# XL_N76E003K2__POWER_V17.net
KiCad netlist of a schematic drawn in Altium Designer
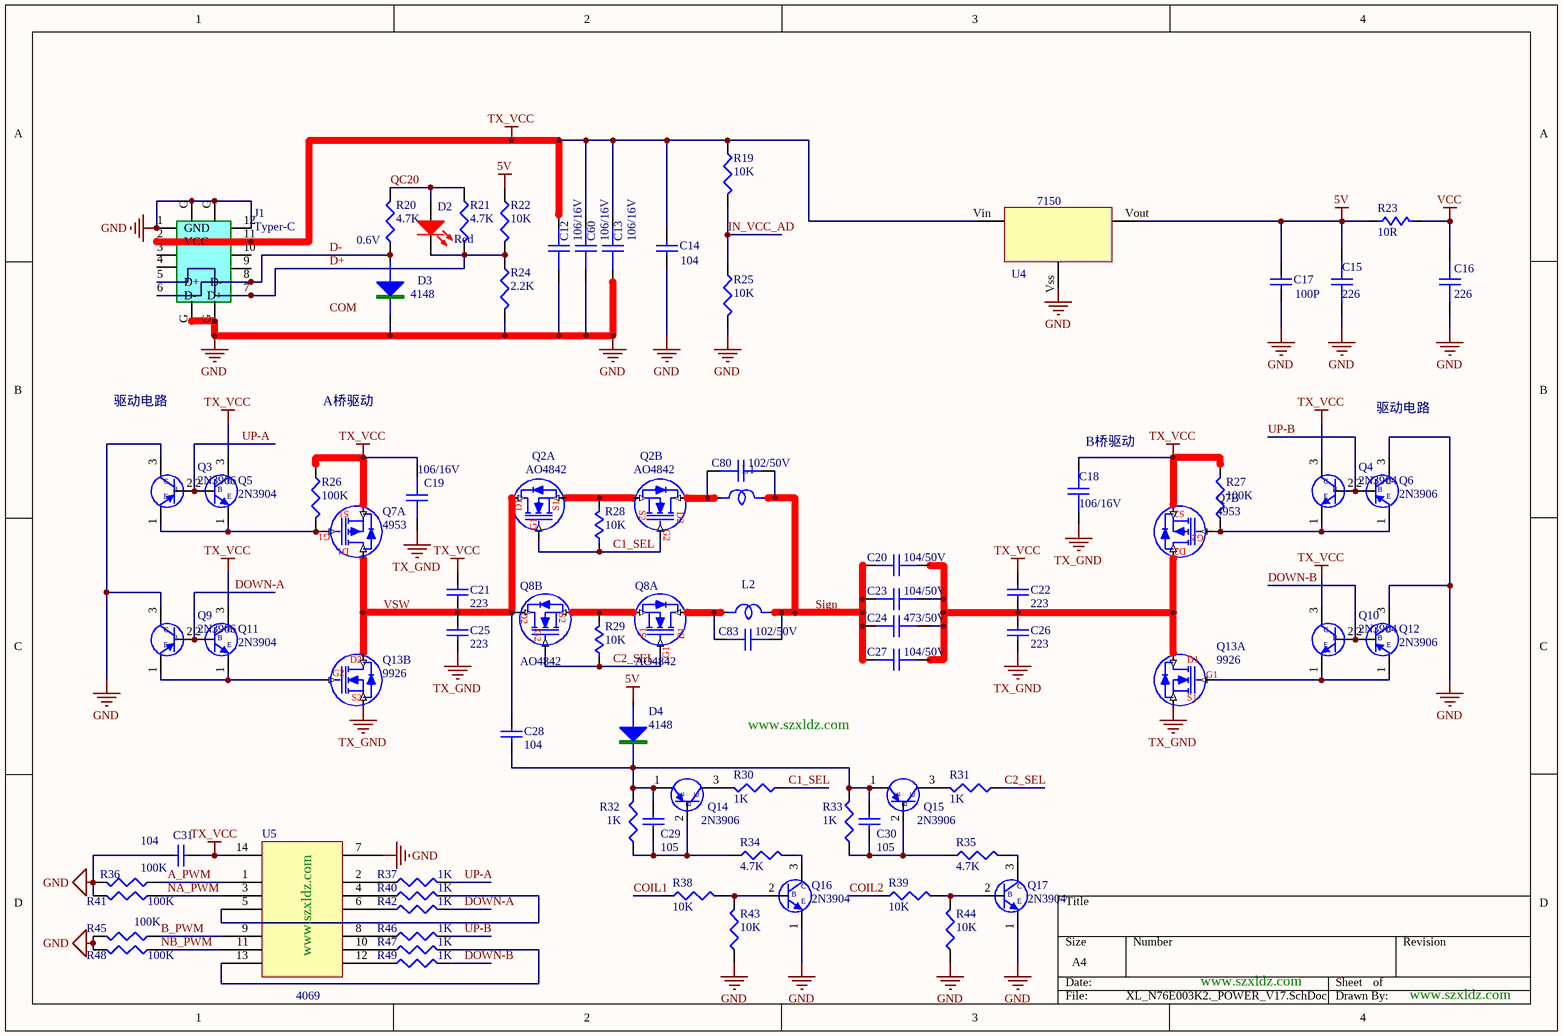
[diagram p0: XL_N76E003K2._POWER_V17.SchDoc]

(export (version "E")
  (design (tool "Eeschema 10.0.6"))
  (components
    (comp (ref "C12") (value "106/16V") (footprint "C0805") (libsource (lib "*") (part "CH")))
    (comp (ref "C13") (value "106/16V") (footprint "C0805") (libsource (lib "*") (part "CH")))
    (comp (ref "C14")
      (value "104")
      (footprint "C0402")
      (description "Capacitor")
      (fields (field (name "PUBLISHER") "Altium Limited"))
      (libsource (lib "*") (part "Cap"))
    )
    (comp (ref "C15") (value "226") (footprint "C0805") (libsource (lib "*") (part "CH")))
    (comp (ref "C16") (value "226") (footprint "C0805") (libsource (lib "*") (part "CH")))
    (comp (ref "C17")
      (value "100P")
      (footprint "C0402")
      (description "Capacitor")
      (fields (field (name "PUBLISHER") "Altium Limited"))
      (libsource (lib "*") (part "Cap"))
    )
    (comp (ref "C18") (value "106/16V") (footprint "C0805") (libsource (lib "*") (part "CH")))
    (comp (ref "C19") (value "106/16V") (footprint "C0805") (libsource (lib "*") (part "CH")))
    (comp (ref "C20") (value "104/50V") (footprint "C1206") (libsource (lib "*") (part "CH")))
    (comp (ref "C21")
      (value "223")
      (footprint "C0603")
      (description "Capacitor")
      (fields (field (name "PUBLISHER") "Altium Limited"))
      (libsource (lib "*") (part "Cap"))
    )
    (comp (ref "C22")
      (value "223")
      (footprint "C1206")
      (description "Capacitor")
      (fields (field (name "PUBLISHER") "Altium Limited"))
      (libsource (lib "*") (part "Cap"))
    )
    (comp (ref "C23") (value "104/50V") (footprint "C1206") (libsource (lib "*") (part "CH")))
    (comp (ref "C24") (value "473/50V") (footprint "C1206") (libsource (lib "*") (part "CH")))
    (comp (ref "C25")
      (value "223")
      (footprint "C0603")
      (description "Capacitor")
      (fields (field (name "PUBLISHER") "Altium Limited"))
      (libsource (lib "*") (part "Cap"))
    )
    (comp (ref "C26")
      (value "223")
      (footprint "C1206")
      (description "Capacitor")
      (fields (field (name "PUBLISHER") "Altium Limited"))
      (libsource (lib "*") (part "Cap"))
    )
    (comp (ref "C27") (value "104/50V") (footprint "C1206") (libsource (lib "*") (part "CH")))
    (comp (ref "C28")
      (value "104")
      (footprint "C0402")
      (description "Capacitor")
      (fields (field (name "PUBLISHER") "Altium Limited"))
      (libsource (lib "*") (part "Cap"))
    )
    (comp (ref "C29")
      (value "105")
      (footprint "C0402")
      (description "Capacitor")
      (fields (field (name "PUBLISHER") "Altium Limited"))
      (libsource (lib "*") (part "Cap"))
    )
    (comp (ref "C30")
      (value "105")
      (footprint "C0402")
      (description "Capacitor")
      (fields (field (name "PUBLISHER") "Altium Limited"))
      (libsource (lib "*") (part "Cap"))
    )
    (comp (ref "C31")
      (value "104")
      (footprint "C0402")
      (description "Capacitor")
      (fields (field (name "PUBLISHER") "Altium Limited"))
      (libsource (lib "*") (part "Cap"))
    )
    (comp (ref "C60") (value "106/16V") (footprint "C0805") (libsource (lib "*") (part "CH")))
    (comp (ref "C80") (value "102/50V") (footprint "C1206") (libsource (lib "*") (part "CH")))
    (comp (ref "C83") (value "102/50V") (footprint "C1206") (libsource (lib "*") (part "CH")))
    (comp (ref "D2") (value "Red") (footprint "LED0603") (libsource (lib "XiaoQiang") (part "LED02")))
    (comp (ref "D3")
      (value "4148")
      (footprint "SOD323")
      (description "1N4001")
      (libsource (lib "*") (part "D0"))
    )
    (comp (ref "D4")
      (value "4148")
      (footprint "SOD323")
      (description "1N4001")
      (libsource (lib "*") (part "D0"))
    )
    (comp (ref "J1") (value "Typer-C") (footprint "USB -MRO17") (libsource (lib "Xin Lang") (part "USB12P")))
    (comp (ref "L1") (value "~") (footprint "L5mm") (description "1uH") (libsource (lib "*") (part "L")))
    (comp (ref "L2") (value "~") (footprint "L5mm") (description "1uH") (libsource (lib "*") (part "L")))
    (comp (ref "Q2") (value "AO4842") (footprint "SOP8D") (libsource (lib "lxzschlib") (part "MOSFETN2")))
    (comp (ref "Q3") (value "2N3906") (footprint "SOT-23") (libsource (lib "") (part "PNP01_1")))
    (comp (ref "Q4") (value "2N3904") (footprint "SOT-23") (libsource (lib "") (part "NPN01_1")))
    (comp (ref "Q5") (value "2N3904") (footprint "SOT-23") (libsource (lib "Xin Lang") (part "NPN01")))
    (comp (ref "Q6") (value "2N3906") (footprint "SOT-23") (libsource (lib "Xin Lang") (part "PNP01")))
    (comp (ref "Q7") (value "4953") (footprint "SOP8D") (libsource (lib "lxzschlib") (part "MOSFETP2")))
    (comp (ref "Q8") (value "AO4842") (footprint "SOP8D") (libsource (lib "") (part "MOSFETN2_1")))
    (comp (ref "Q9") (value "2N3906") (footprint "SOT-23") (libsource (lib "") (part "PNP01_1")))
    (comp (ref "Q10") (value "2N3904") (footprint "SOT-23") (libsource (lib "") (part "NPN01_1")))
    (comp (ref "Q11") (value "2N3904") (footprint "SOT-23") (libsource (lib "Xin Lang") (part "NPN01")))
    (comp (ref "Q12") (value "2N3906") (footprint "SOT-23") (libsource (lib "Xin Lang") (part "PNP01")))
    (comp (ref "Q13") (value "9926") (footprint "SOP8D") (libsource (lib "lxzschlib") (part "MOSFETN2")))
    (comp (ref "Q14") (value "2N3906") (footprint "SOT-23") (libsource (lib "XiaoQiang") (part "PNP01")))
    (comp (ref "Q15") (value "2N3906") (footprint "SOT-23") (libsource (lib "XiaoQiang") (part "PNP01")))
    (comp (ref "Q16") (value "2N3904") (footprint "SOT-23") (libsource (lib "XiaoQiang") (part "NPN01")))
    (comp (ref "Q17") (value "2N3904") (footprint "SOT-23") (libsource (lib "XiaoQiang") (part "NPN01")))
    (comp (ref "R19") (value "10K") (footprint "R0402") (description "1K") (libsource (lib "*") (part "R")))
    (comp (ref "R20") (value "4.7K") (footprint "R0402") (description "1K") (libsource (lib "*") (part "R")))
    (comp (ref "R21") (value "4.7K") (footprint "R0402") (description "1K") (libsource (lib "*") (part "R")))
    (comp (ref "R22") (value "10K") (footprint "R0402") (description "1K") (libsource (lib "*") (part "R")))
    (comp (ref "R23") (value "10R") (footprint "R0402") (libsource (lib "Xin Lang") (part "Res01")))
    (comp (ref "R24") (value "2.2K") (footprint "R0402") (description "1K") (libsource (lib "*") (part "R")))
    (comp (ref "R25") (value "10K") (footprint "R0402") (description "1K") (libsource (lib "*") (part "R")))
    (comp (ref "R26") (value "100K") (footprint "R0402") (description "1K") (libsource (lib "*") (part "R")))
    (comp (ref "R27") (value "100K") (footprint "R0402") (description "1K") (libsource (lib "*") (part "R")))
    (comp (ref "R28") (value "10K") (footprint "R0402") (libsource (lib "XiaoQiang") (part "Res01")))
    (comp (ref "R29") (value "10K") (footprint "R0402") (libsource (lib "XiaoQiang") (part "Res01")))
    (comp (ref "R30") (value "1K") (footprint "R0402") (libsource (lib "*") (part "R")))
    (comp (ref "R31") (value "1K") (footprint "R0402") (libsource (lib "*") (part "R")))
    (comp (ref "R32") (value "1K") (footprint "R0402") (libsource (lib "*") (part "R")))
    (comp (ref "R33") (value "1K") (footprint "R0402") (libsource (lib "*") (part "R")))
    (comp (ref "R34") (value "4.7K") (footprint "R0402") (description "1K") (libsource (lib "*") (part "R")))
    (comp (ref "R35") (value "4.7K") (footprint "R0402") (description "1K") (libsource (lib "*") (part "R")))
    (comp (ref "R36") (value "100K") (footprint "R0402") (description "1K") (libsource (lib "*") (part "R")))
    (comp (ref "R37") (value "1K") (footprint "R0402") (libsource (lib "*") (part "R")))
    (comp (ref "R38") (value "10K") (footprint "R0402") (description "1K") (libsource (lib "*") (part "R")))
    (comp (ref "R39") (value "10K") (footprint "R0402") (description "1K") (libsource (lib "*") (part "R")))
    (comp (ref "R40") (value "1K") (footprint "R0402") (libsource (lib "*") (part "R")))
    (comp (ref "R41") (value "100K") (footprint "R0402") (description "1K") (libsource (lib "*") (part "R")))
    (comp (ref "R42") (value "1K") (footprint "R0402") (libsource (lib "*") (part "R")))
    (comp (ref "R43") (value "10K") (footprint "R0402") (description "1K") (libsource (lib "*") (part "R")))
    (comp (ref "R44") (value "10K") (footprint "R0402") (description "1K") (libsource (lib "*") (part "R")))
    (comp (ref "R45") (value "100K") (footprint "R0402") (description "1K") (libsource (lib "*") (part "R")))
    (comp (ref "R46") (value "1K") (footprint "R0402") (libsource (lib "*") (part "R")))
    (comp (ref "R47") (value "1K") (footprint "R0402") (libsource (lib "*") (part "R")))
    (comp (ref "R48") (value "100K") (footprint "R0402") (description "1K") (libsource (lib "*") (part "R")))
    (comp (ref "R49") (value "1K") (footprint "R0402") (libsource (lib "*") (part "R")))
    (comp (ref "U4") (value "7150") (footprint "SOT89a") (libsource (lib "*") (part "VOLTREG")))
    (comp (ref "U5") (value "4069") (footprint "SOP14") (libsource (lib "Schlib1") (part "CD4069")))
  )
  (nets
    (net (code "1") (name "/A_PWM") (class "Default")
      (node (ref "R36") (pin "1") (pintype "passive"))
      (node (ref "U5") (pin "1") (pintype "passive"))
    )
    (net (code "2") (name "/B_PWM") (class "Default")
      (node (ref "R45") (pin "1") (pintype "passive"))
      (node (ref "U5") (pin "9") (pintype "passive"))
    )
    (net (code "3") (name "/C1_SEL") (class "Default")
      (node (ref "Q2") (pin "B1") (pinfunction "G1_B1") (pintype "input"))
      (node (ref "Q2") (pin "B2") (pinfunction "G2_B2") (pintype "input"))
      (node (ref "R28") (pin "1") (pinfunction "1_1") (pintype "passive"))
      (node (ref "R30") (pin "1") (pintype "passive"))
    )
    (net (code "4") (name "/C2_SEL") (class "Default")
      (node (ref "Q8") (pin "B1") (pinfunction "G1_B1") (pintype "input"))
      (node (ref "Q8") (pin "B2") (pinfunction "G2_B2") (pintype "input"))
      (node (ref "R29") (pin "1") (pinfunction "1_1") (pintype "passive"))
      (node (ref "R31") (pin "1") (pintype "passive"))
    )
    (net (code "5") (name "/COIL1") (class "Default") (node (ref "R38") (pin "1") (pintype "passive")))
    (net (code "6") (name "/COIL2") (class "Default") (node (ref "R39") (pin "1") (pintype "passive")))
    (net (code "8") (name "/D+") (class "Default")
      (node (ref "D2") (pin "2") (pinfunction "K_2") (pintype "passive"))
      (node (ref "J1") (pin "5") (pinfunction "D+_5") (pintype "passive"))
      (node (ref "J1") (pin "7") (pinfunction "D+_7") (pintype "passive"))
      (node (ref "R21") (pin "1") (pintype "passive"))
      (node (ref "R22") (pin "1") (pintype "passive"))
      (node (ref "R24") (pin "2") (pintype "passive"))
    )
    (net (code "9") (name "/D-") (class "Default")
      (node (ref "D3") (pin "1") (pintype "passive"))
      (node (ref "J1") (pin "6") (pinfunction "D-_6") (pintype "passive"))
      (node (ref "J1") (pin "8") (pinfunction "D-_8") (pintype "passive"))
      (node (ref "R20") (pin "2") (pintype "passive"))
    )
    (net (code "10") (name "/DOWN-A") (class "Default")
      (node (ref "Q11") (pin "2") (pinfunction "B_2") (pintype "passive"))
      (node (ref "Q9") (pin "2") (pinfunction "B_2") (pintype "passive"))
      (node (ref "R42") (pin "2") (pintype "passive"))
    )
    (net (code "11") (name "/DOWN-B") (class "Default")
      (node (ref "Q10") (pin "2") (pinfunction "B_2") (pintype "passive"))
      (node (ref "Q12") (pin "2") (pinfunction "B_2") (pintype "passive"))
      (node (ref "R49") (pin "2") (pintype "passive"))
    )
    (net (code "12") (name "/IN_VCC_AD") (class "Default")
      (node (ref "R19") (pin "1") (pintype "passive"))
      (node (ref "R25") (pin "2") (pintype "passive"))
    )
    (net (code "13") (name "/NA_PWM") (class "Default")
      (node (ref "R41") (pin "1") (pintype "passive"))
      (node (ref "U5") (pin "3") (pintype "passive"))
    )
    (net (code "14") (name "/NB_PWM") (class "Default")
      (node (ref "R48") (pin "1") (pintype "passive"))
      (node (ref "U5") (pin "11") (pintype "passive"))
    )
    (net (code "15") (name "/QC20") (class "Default")
      (node (ref "D2") (pin "1") (pinfunction "A_1") (pintype "passive"))
      (node (ref "R20") (pin "1") (pintype "passive"))
      (node (ref "R21") (pin "2") (pintype "passive"))
    )
    (net (code "16") (name "/Sign") (class "Default")
      (node (ref "C20") (pin "1") (pintype "passive"))
      (node (ref "C23") (pin "1") (pintype "passive"))
      (node (ref "C24") (pin "1") (pintype "passive"))
      (node (ref "C27") (pin "1") (pintype "passive"))
      (node (ref "C80") (pin "2") (pintype "passive"))
      (node (ref "C83") (pin "2") (pintype "passive"))
      (node (ref "L1") (pin "2") (pintype "passive"))
      (node (ref "L2") (pin "2") (pintype "passive"))
    )
    (net (code "17") (name "/UP-A") (class "Default")
      (node (ref "Q3") (pin "2") (pinfunction "B_2") (pintype "passive"))
      (node (ref "Q5") (pin "2") (pinfunction "B_2") (pintype "passive"))
      (node (ref "R37") (pin "2") (pintype "passive"))
    )
    (net (code "18") (name "/UP-B") (class "Default")
      (node (ref "Q4") (pin "2") (pinfunction "B_2") (pintype "passive"))
      (node (ref "Q6") (pin "2") (pinfunction "B_2") (pintype "passive"))
      (node (ref "R46") (pin "2") (pintype "passive"))
    )
    (net (code "19") (name "/VSW") (class "Default")
      (node (ref "C21") (pin "1") (pinfunction "1_1") (pintype "passive"))
      (node (ref "C25") (pin "2") (pinfunction "2_2") (pintype "passive"))
      (node (ref "C28") (pin "1") (pinfunction "1_1") (pintype "passive"))
      (node (ref "Q13") (pin "C2") (pinfunction "D2_C2") (pintype "input"))
      (node (ref "Q2") (pin "C1") (pinfunction "D1_C1") (pintype "input"))
      (node (ref "Q7") (pin "C1") (pinfunction "D1_C1") (pintype "input"))
      (node (ref "Q8") (pin "C2") (pinfunction "D2_C2") (pintype "input"))
    )
    (net (code "20") (name "5V") (class "Default")
      (node (ref "C15") (pin "1") (pintype "passive"))
      (node (ref "C17") (pin "1") (pinfunction "1_1") (pintype "passive"))
      (node (ref "D4") (pin "1") (pintype "passive"))
      (node (ref "R22") (pin "2") (pintype "passive"))
      (node (ref "R23") (pin "1") (pinfunction "1_1") (pintype "passive"))
      (node (ref "U4") (pin "Vout") (pintype "passive"))
    )
    (net (code "21") (name "GND") (class "Default")
      (node (ref "C12") (pin "2") (pintype "passive"))
      (node (ref "C13") (pin "2") (pintype "passive"))
      (node (ref "C14") (pin "2") (pinfunction "2_2") (pintype "passive"))
      (node (ref "C15") (pin "2") (pintype "passive"))
      (node (ref "C16") (pin "1") (pintype "passive"))
      (node (ref "C17") (pin "2") (pinfunction "2_2") (pintype "passive"))
      (node (ref "C31") (pin "1") (pinfunction "1_1") (pintype "passive"))
      (node (ref "C60") (pin "2") (pintype "passive"))
      (node (ref "D3") (pin "2") (pintype "passive"))
      (node (ref "J1") (pin "1") (pinfunction "GND_1") (pintype "passive"))
      (node (ref "J1") (pin "12") (pintype "passive"))
      (node (ref "J1") (pin "G") (pintype "passive"))
      (node (ref "Q12") (pin "3") (pinfunction "C_3") (pintype "passive"))
      (node (ref "Q16") (pin "1") (pinfunction "E_1") (pintype "passive"))
      (node (ref "Q17") (pin "1") (pinfunction "E_1") (pintype "passive"))
      (node (ref "Q3") (pin "3") (pinfunction "C_3") (pintype "passive"))
      (node (ref "Q6") (pin "3") (pinfunction "C_3") (pintype "passive"))
      (node (ref "Q9") (pin "3") (pinfunction "C_3") (pintype "passive"))
      (node (ref "R24") (pin "1") (pintype "passive"))
      (node (ref "R25") (pin "1") (pintype "passive"))
      (node (ref "R36") (pin "2") (pintype "passive"))
      (node (ref "R41") (pin "2") (pintype "passive"))
      (node (ref "R43") (pin "1") (pintype "passive"))
      (node (ref "R44") (pin "1") (pintype "passive"))
      (node (ref "R45") (pin "2") (pintype "passive"))
      (node (ref "R48") (pin "2") (pintype "passive"))
      (node (ref "U4") (pin "Vss") (pintype "passive"))
      (node (ref "U5") (pin "7") (pintype "passive"))
    )
    (net (code "22") (name "Net-(Q2A-S1)") (class "Default")
      (node (ref "Q2") (pin "E1") (pinfunction "S1_E1") (pintype "input"))
      (node (ref "Q2") (pin "E2") (pinfunction "S2_E2") (pintype "input"))
      (node (ref "R28") (pin "2") (pinfunction "2_2") (pintype "passive"))
    )
    (net (code "23") (name "Net-(Q2B-D2)") (class "Default")
      (node (ref "C80") (pin "1") (pintype "passive"))
      (node (ref "L1") (pin "1") (pintype "passive"))
      (node (ref "Q2") (pin "C2") (pinfunction "D2_C2") (pintype "input"))
    )
    (net (code "24") (name "Net-(Q3-E)") (class "Default")
      (node (ref "Q3") (pin "1") (pinfunction "E_1") (pintype "passive"))
      (node (ref "Q5") (pin "1") (pinfunction "E_1") (pintype "passive"))
      (node (ref "Q7") (pin "B1") (pinfunction "G1_B1") (pintype "input"))
      (node (ref "R26") (pin "2") (pintype "passive"))
    )
    (net (code "25") (name "Net-(Q4-E)") (class "Default")
      (node (ref "Q4") (pin "1") (pinfunction "E_1") (pintype "passive"))
      (node (ref "Q6") (pin "1") (pinfunction "E_1") (pintype "passive"))
      (node (ref "Q7") (pin "B2") (pinfunction "G2_B2") (pintype "input"))
      (node (ref "R27") (pin "1") (pintype "passive"))
    )
    (net (code "26") (name "Net-(Q8A-D1)") (class "Default")
      (node (ref "C83") (pin "1") (pintype "passive"))
      (node (ref "L2") (pin "1") (pintype "passive"))
      (node (ref "Q8") (pin "C1") (pinfunction "D1_C1") (pintype "input"))
    )
    (net (code "27") (name "Net-(Q8A-S1)") (class "Default")
      (node (ref "Q8") (pin "E1") (pinfunction "S1_E1") (pintype "input"))
      (node (ref "Q8") (pin "E2") (pinfunction "S2_E2") (pintype "input"))
      (node (ref "R29") (pin "2") (pinfunction "2_2") (pintype "passive"))
    )
    (net (code "28") (name "Net-(Q10-E)") (class "Default")
      (node (ref "Q10") (pin "1") (pinfunction "E_1") (pintype "passive"))
      (node (ref "Q12") (pin "1") (pinfunction "E_1") (pintype "passive"))
      (node (ref "Q13") (pin "B1") (pinfunction "G1_B1") (pintype "input"))
    )
    (net (code "29") (name "Net-(Q11-E)") (class "Default")
      (node (ref "Q11") (pin "1") (pinfunction "E_1") (pintype "passive"))
      (node (ref "Q13") (pin "B2") (pinfunction "G2_B2") (pintype "input"))
      (node (ref "Q9") (pin "1") (pinfunction "E_1") (pintype "passive"))
    )
    (net (code "30") (name "Net-(Q13A-D1)") (class "Default")
      (node (ref "C20") (pin "2") (pintype "passive"))
      (node (ref "C22") (pin "1") (pinfunction "1_1") (pintype "passive"))
      (node (ref "C23") (pin "2") (pintype "passive"))
      (node (ref "C24") (pin "2") (pintype "passive"))
      (node (ref "C26") (pin "2") (pinfunction "2_2") (pintype "passive"))
      (node (ref "C27") (pin "2") (pintype "passive"))
      (node (ref "Q13") (pin "C1") (pinfunction "D1_C1") (pintype "input"))
      (node (ref "Q7") (pin "C2") (pinfunction "D2_C2") (pintype "input"))
    )
    (net (code "31") (name "Net-(Q14-B)") (class "Default")
      (node (ref "C29") (pin "2") (pinfunction "2_2") (pintype "passive"))
      (node (ref "Q14") (pin "2") (pinfunction "B_2") (pintype "passive"))
      (node (ref "R32") (pin "1") (pintype "passive"))
      (node (ref "R34") (pin "1") (pintype "passive"))
    )
    (net (code "32") (name "Net-(Q14-C)") (class "Default")
      (node (ref "Q14") (pin "3") (pinfunction "C_3") (pintype "passive"))
      (node (ref "R30") (pin "2") (pintype "passive"))
    )
    (net (code "33") (name "Net-(Q14-E)") (class "Default")
      (node (ref "C28") (pin "2") (pinfunction "2_2") (pintype "passive"))
      (node (ref "C29") (pin "1") (pinfunction "1_1") (pintype "passive"))
      (node (ref "C30") (pin "1") (pinfunction "1_1") (pintype "passive"))
      (node (ref "D4") (pin "2") (pintype "passive"))
      (node (ref "Q14") (pin "1") (pinfunction "E_1") (pintype "passive"))
      (node (ref "Q15") (pin "1") (pinfunction "E_1") (pintype "passive"))
      (node (ref "R32") (pin "2") (pintype "passive"))
      (node (ref "R33") (pin "2") (pintype "passive"))
    )
    (net (code "34") (name "Net-(Q15-B)") (class "Default")
      (node (ref "C30") (pin "2") (pinfunction "2_2") (pintype "passive"))
      (node (ref "Q15") (pin "2") (pinfunction "B_2") (pintype "passive"))
      (node (ref "R33") (pin "1") (pintype "passive"))
      (node (ref "R35") (pin "1") (pintype "passive"))
    )
    (net (code "35") (name "Net-(Q15-C)") (class "Default")
      (node (ref "Q15") (pin "3") (pinfunction "C_3") (pintype "passive"))
      (node (ref "R31") (pin "2") (pintype "passive"))
    )
    (net (code "36") (name "Net-(Q16-B)") (class "Default")
      (node (ref "Q16") (pin "2") (pinfunction "B_2") (pintype "passive"))
      (node (ref "R38") (pin "2") (pintype "passive"))
      (node (ref "R43") (pin "2") (pintype "passive"))
    )
    (net (code "37") (name "Net-(Q16-C)") (class "Default")
      (node (ref "Q16") (pin "3") (pinfunction "C_3") (pintype "passive"))
      (node (ref "R34") (pin "2") (pintype "passive"))
    )
    (net (code "38") (name "Net-(Q17-B)") (class "Default")
      (node (ref "Q17") (pin "2") (pinfunction "B_2") (pintype "passive"))
      (node (ref "R39") (pin "2") (pintype "passive"))
      (node (ref "R44") (pin "2") (pintype "passive"))
    )
    (net (code "39") (name "Net-(Q17-C)") (class "Default")
      (node (ref "Q17") (pin "3") (pinfunction "C_3") (pintype "passive"))
      (node (ref "R35") (pin "2") (pintype "passive"))
    )
    (net (code "40") (name "Net-(R37-Pad1)") (class "Default")
      (node (ref "R37") (pin "1") (pintype "passive"))
      (node (ref "U5") (pin "2") (pintype "passive"))
    )
    (net (code "41") (name "Net-(R40-Pad1)") (class "Default")
      (node (ref "R40") (pin "1") (pintype "passive"))
      (node (ref "U5") (pin "4") (pintype "passive"))
    )
    (net (code "42") (name "Net-(R40-Pad2)") (class "Default")
      (node (ref "R40") (pin "2") (pintype "passive"))
      (node (ref "U5") (pin "5") (pintype "passive"))
    )
    (net (code "43") (name "Net-(R42-Pad1)") (class "Default")
      (node (ref "R42") (pin "1") (pintype "passive"))
      (node (ref "U5") (pin "6") (pintype "passive"))
    )
    (net (code "44") (name "Net-(R46-Pad1)") (class "Default")
      (node (ref "R46") (pin "1") (pintype "passive"))
      (node (ref "U5") (pin "8") (pintype "passive"))
    )
    (net (code "45") (name "Net-(R47-Pad1)") (class "Default")
      (node (ref "R47") (pin "1") (pintype "passive"))
      (node (ref "U5") (pin "10") (pintype "passive"))
    )
    (net (code "46") (name "Net-(R47-Pad2)") (class "Default")
      (node (ref "R47") (pin "2") (pintype "passive"))
      (node (ref "U5") (pin "13") (pintype "passive"))
    )
    (net (code "47") (name "Net-(R49-Pad1)") (class "Default")
      (node (ref "R49") (pin "1") (pintype "passive"))
      (node (ref "U5") (pin "12") (pintype "passive"))
    )
    (net (code "48") (name "TX_GND") (class "Default")
      (node (ref "C18") (pin "2") (pintype "passive"))
      (node (ref "C19") (pin "2") (pintype "passive"))
      (node (ref "C25") (pin "1") (pinfunction "1_1") (pintype "passive"))
      (node (ref "C26") (pin "1") (pinfunction "1_1") (pintype "passive"))
      (node (ref "Q13") (pin "E1") (pinfunction "S1_E1") (pintype "input"))
      (node (ref "Q13") (pin "E2") (pinfunction "S2_E2") (pintype "input"))
    )
    (net (code "49") (name "TX_VCC") (class "Default")
      (node (ref "C12") (pin "1") (pintype "passive"))
      (node (ref "C13") (pin "1") (pintype "passive"))
      (node (ref "C14") (pin "1") (pinfunction "1_1") (pintype "passive"))
      (node (ref "C18") (pin "1") (pintype "passive"))
      (node (ref "C19") (pin "1") (pintype "passive"))
      (node (ref "C21") (pin "2") (pinfunction "2_2") (pintype "passive"))
      (node (ref "C22") (pin "2") (pinfunction "2_2") (pintype "passive"))
      (node (ref "C31") (pin "2") (pinfunction "2_2") (pintype "passive"))
      (node (ref "C60") (pin "1") (pintype "passive"))
      (node (ref "J1") (pin "11") (pintype "passive"))
      (node (ref "J1") (pin "2") (pinfunction "VCC_2") (pintype "passive"))
      (node (ref "Q10") (pin "3") (pinfunction "C_3") (pintype "passive"))
      (node (ref "Q11") (pin "3") (pinfunction "C_3") (pintype "passive"))
      (node (ref "Q4") (pin "3") (pinfunction "C_3") (pintype "passive"))
      (node (ref "Q5") (pin "3") (pinfunction "C_3") (pintype "passive"))
      (node (ref "Q7") (pin "E1") (pinfunction "S1_E1") (pintype "input"))
      (node (ref "Q7") (pin "E2") (pinfunction "S2_E2") (pintype "input"))
      (node (ref "R19") (pin "2") (pintype "passive"))
      (node (ref "R26") (pin "1") (pintype "passive"))
      (node (ref "R27") (pin "2") (pintype "passive"))
      (node (ref "U4") (pin "Vin") (pintype "passive"))
      (node (ref "U5") (pin "14") (pintype "passive"))
    )
    (net (code "50") (name "VCC") (class "Default")
      (node (ref "C16") (pin "2") (pintype "passive"))
      (node (ref "R23") (pin "2") (pinfunction "2_2") (pintype "passive"))
    )
    (net (code "51") (name "unconnected-(J1-Pad3)") (class "Default")
      (node (ref "J1") (pin "3") (pintype "passive"))
    )
    (net (code "52") (name "unconnected-(J1-Pad4)") (class "Default")
      (node (ref "J1") (pin "4") (pintype "passive"))
    )
    (net (code "53") (name "unconnected-(J1-Pad9)") (class "Default")
      (node (ref "J1") (pin "9") (pintype "passive"))
    )
    (net (code "54") (name "unconnected-(J1-Pad10)") (class "Default")
      (node (ref "J1") (pin "10") (pintype "passive"))
    )
  )
)
